# MNA6A.net
KiCad netlist of a schematic drawn in Altium Designer
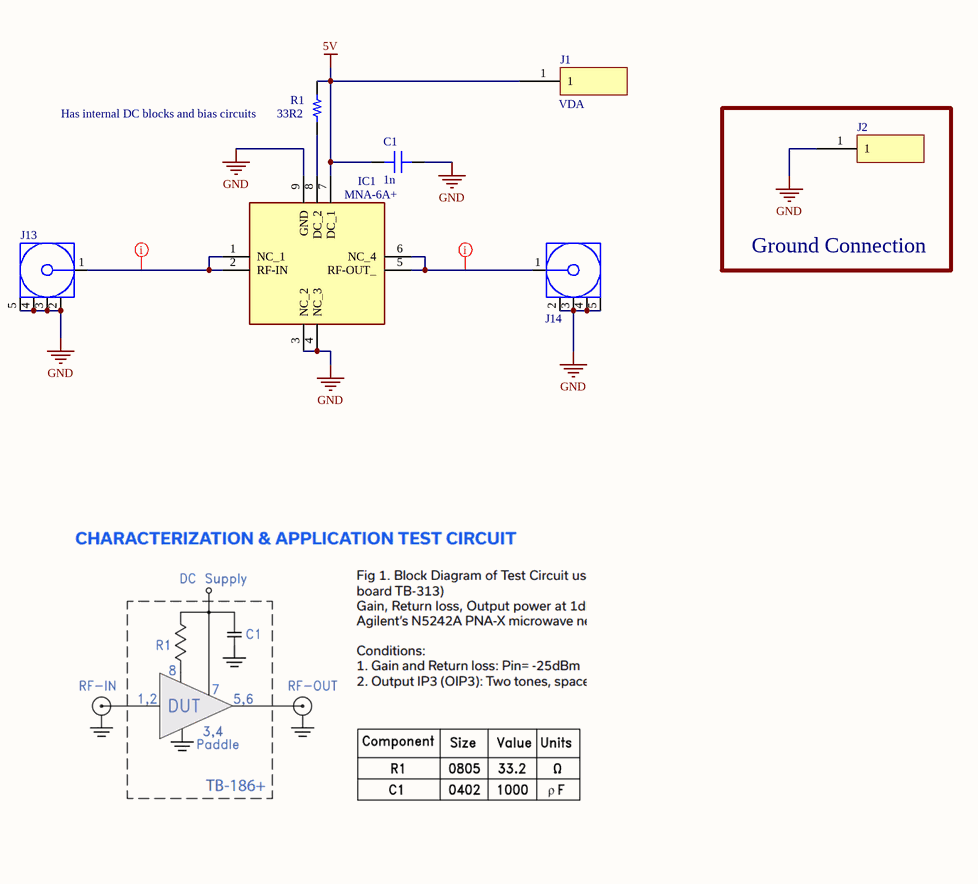
[diagram p0: MNA6A.SchDoc]

(export (version "E")
  (design (tool "Eeschema 10.0.6"))
  (components
    (comp (ref "C1")
      (value "1n")
      (footprint "CAP 0603_1608 RF")
      (description "CAP CER 1000PF 50V 0603")
      (fields (field (name "PART NUMBER") "UMK107SD102JA-T") (field (name "MANUFACTURER") "Taiyo Yuden"))
      (libsource (lib "Celestial Altium Library - altium_library") (part "Capacitor"))
    )
    (comp (ref "IC1")
      (value "MNA-6A+")
      (footprint "SamacSys:MNA6A")
      (description "Integrated Circuit")
      (fields (field (name "MOUSER PART NUMBER") "139-MNA-6A"))
      (libsource (lib "*") (part "MNA-6A+"))
    )
    (comp (ref "J1")
      (value "Nail_Head")
      (footprint "Nail_Head")
      (description "1460-2-00-80-00-00-03-0 Mill-Max")
      (libsource (lib "ARIS_COM_Transponder") (part "Nail_Head"))
    )
    (comp (ref "J2")
      (value "Nail_Head")
      (footprint "Nail_Head")
      (description "1460-2-00-80-00-00-03-0 Mill-Max")
      (libsource (lib "ARIS_COM_Transponder") (part "Nail_Head"))
    )
    (comp (ref "J13")
      (value "60312202114513")
      (footprint "60312202114513")
      (description "WR-SMA Connector, PCB End Launch Jack, 6.35SQ Flange Flat Tab 1.6mm, DC~18GHz, 50Ohm")
      (fields (field (name "MANUFACTURER") "Wurth Elektronik"))
      (libsource (lib "Altium_WR-SMA (rev23a)") (part "60312202114513"))
    )
    (comp (ref "J14")
      (value "60312202114513")
      (footprint "60312202114513")
      (description "WR-SMA Connector, PCB End Launch Jack, 6.35SQ Flange Flat Tab 1.6mm, DC~18GHz, 50Ohm")
      (fields (field (name "MANUFACTURER") "Wurth Elektronik"))
      (libsource (lib "Altium_WR-SMA (rev23a)") (part "60312202114513"))
    )
    (comp (ref "R1")
      (value "33R2")
      (footprint "RES 0805_2012")
      (description "RES SMD 33.2 OHM 1% 1/2W 0805")
      (fields (field (name "PART NUMBER") "RCS080533R2FKEA") (field (name "MANUFACTURER") "Vishay Dale"))
      (libsource (lib "Celestial Altium Library - altium_library") (part "Resistor"))
    )
  )
  (nets
    (net (code "1") (name "5V") (class "Default")
      (node (ref "C1") (pin "1") (pinfunction "1_1") (pintype "passive"))
      (node (ref "IC1") (pin "7") (pinfunction "DC_1_7") (pintype "passive"))
      (node (ref "J1") (pin "1") (pinfunction "1_1") (pintype "passive"))
      (node (ref "R1") (pin "2") (pinfunction "2_2") (pintype "passive"))
    )
    (net (code "2") (name "GND") (class "Default")
      (node (ref "C1") (pin "2") (pinfunction "2_2") (pintype "passive"))
      (node (ref "IC1") (pin "3") (pinfunction "NC_2_3") (pintype "passive"))
      (node (ref "IC1") (pin "4") (pinfunction "NC_3_4") (pintype "passive"))
      (node (ref "IC1") (pin "9") (pinfunction "GND_9") (pintype "passive"))
      (node (ref "J13") (pin "2") (pinfunction "GND_2") (pintype "passive"))
      (node (ref "J13") (pin "3") (pinfunction "GND_3") (pintype "passive"))
      (node (ref "J13") (pin "4") (pinfunction "GND_4") (pintype "passive"))
      (node (ref "J13") (pin "5") (pinfunction "GND_5") (pintype "passive"))
      (node (ref "J14") (pin "2") (pinfunction "GND_2") (pintype "passive"))
      (node (ref "J14") (pin "3") (pinfunction "GND_3") (pintype "passive"))
      (node (ref "J14") (pin "4") (pinfunction "GND_4") (pintype "passive"))
      (node (ref "J14") (pin "5") (pinfunction "GND_5") (pintype "passive"))
      (node (ref "J2") (pin "1") (pinfunction "1_1") (pintype "passive"))
    )
    (net (code "3") (name "Net-(IC1-DC_2)") (class "Default")
      (node (ref "IC1") (pin "8") (pinfunction "DC_2_8") (pintype "passive"))
      (node (ref "R1") (pin "1") (pinfunction "1_1") (pintype "passive"))
    )
    (net (code "4") (name "Net-(IC1-NC_1)") (class "Default")
      (node (ref "IC1") (pin "1") (pinfunction "NC_1_1") (pintype "passive"))
      (node (ref "IC1") (pin "2") (pinfunction "RF-IN_2") (pintype "passive"))
      (node (ref "J13") (pin "1") (pinfunction "Signal_1") (pintype "passive"))
    )
    (net (code "5") (name "Net-(IC1-NC_4)") (class "Default")
      (node (ref "IC1") (pin "5") (pinfunction "RF-OUT__5") (pintype "passive"))
      (node (ref "IC1") (pin "6") (pinfunction "NC_4_6") (pintype "passive"))
      (node (ref "J14") (pin "1") (pinfunction "Signal_1") (pintype "passive"))
    )
  )
)
